# 11_MYIR.net
KiCad netlist of a schematic drawn in Altium Designer
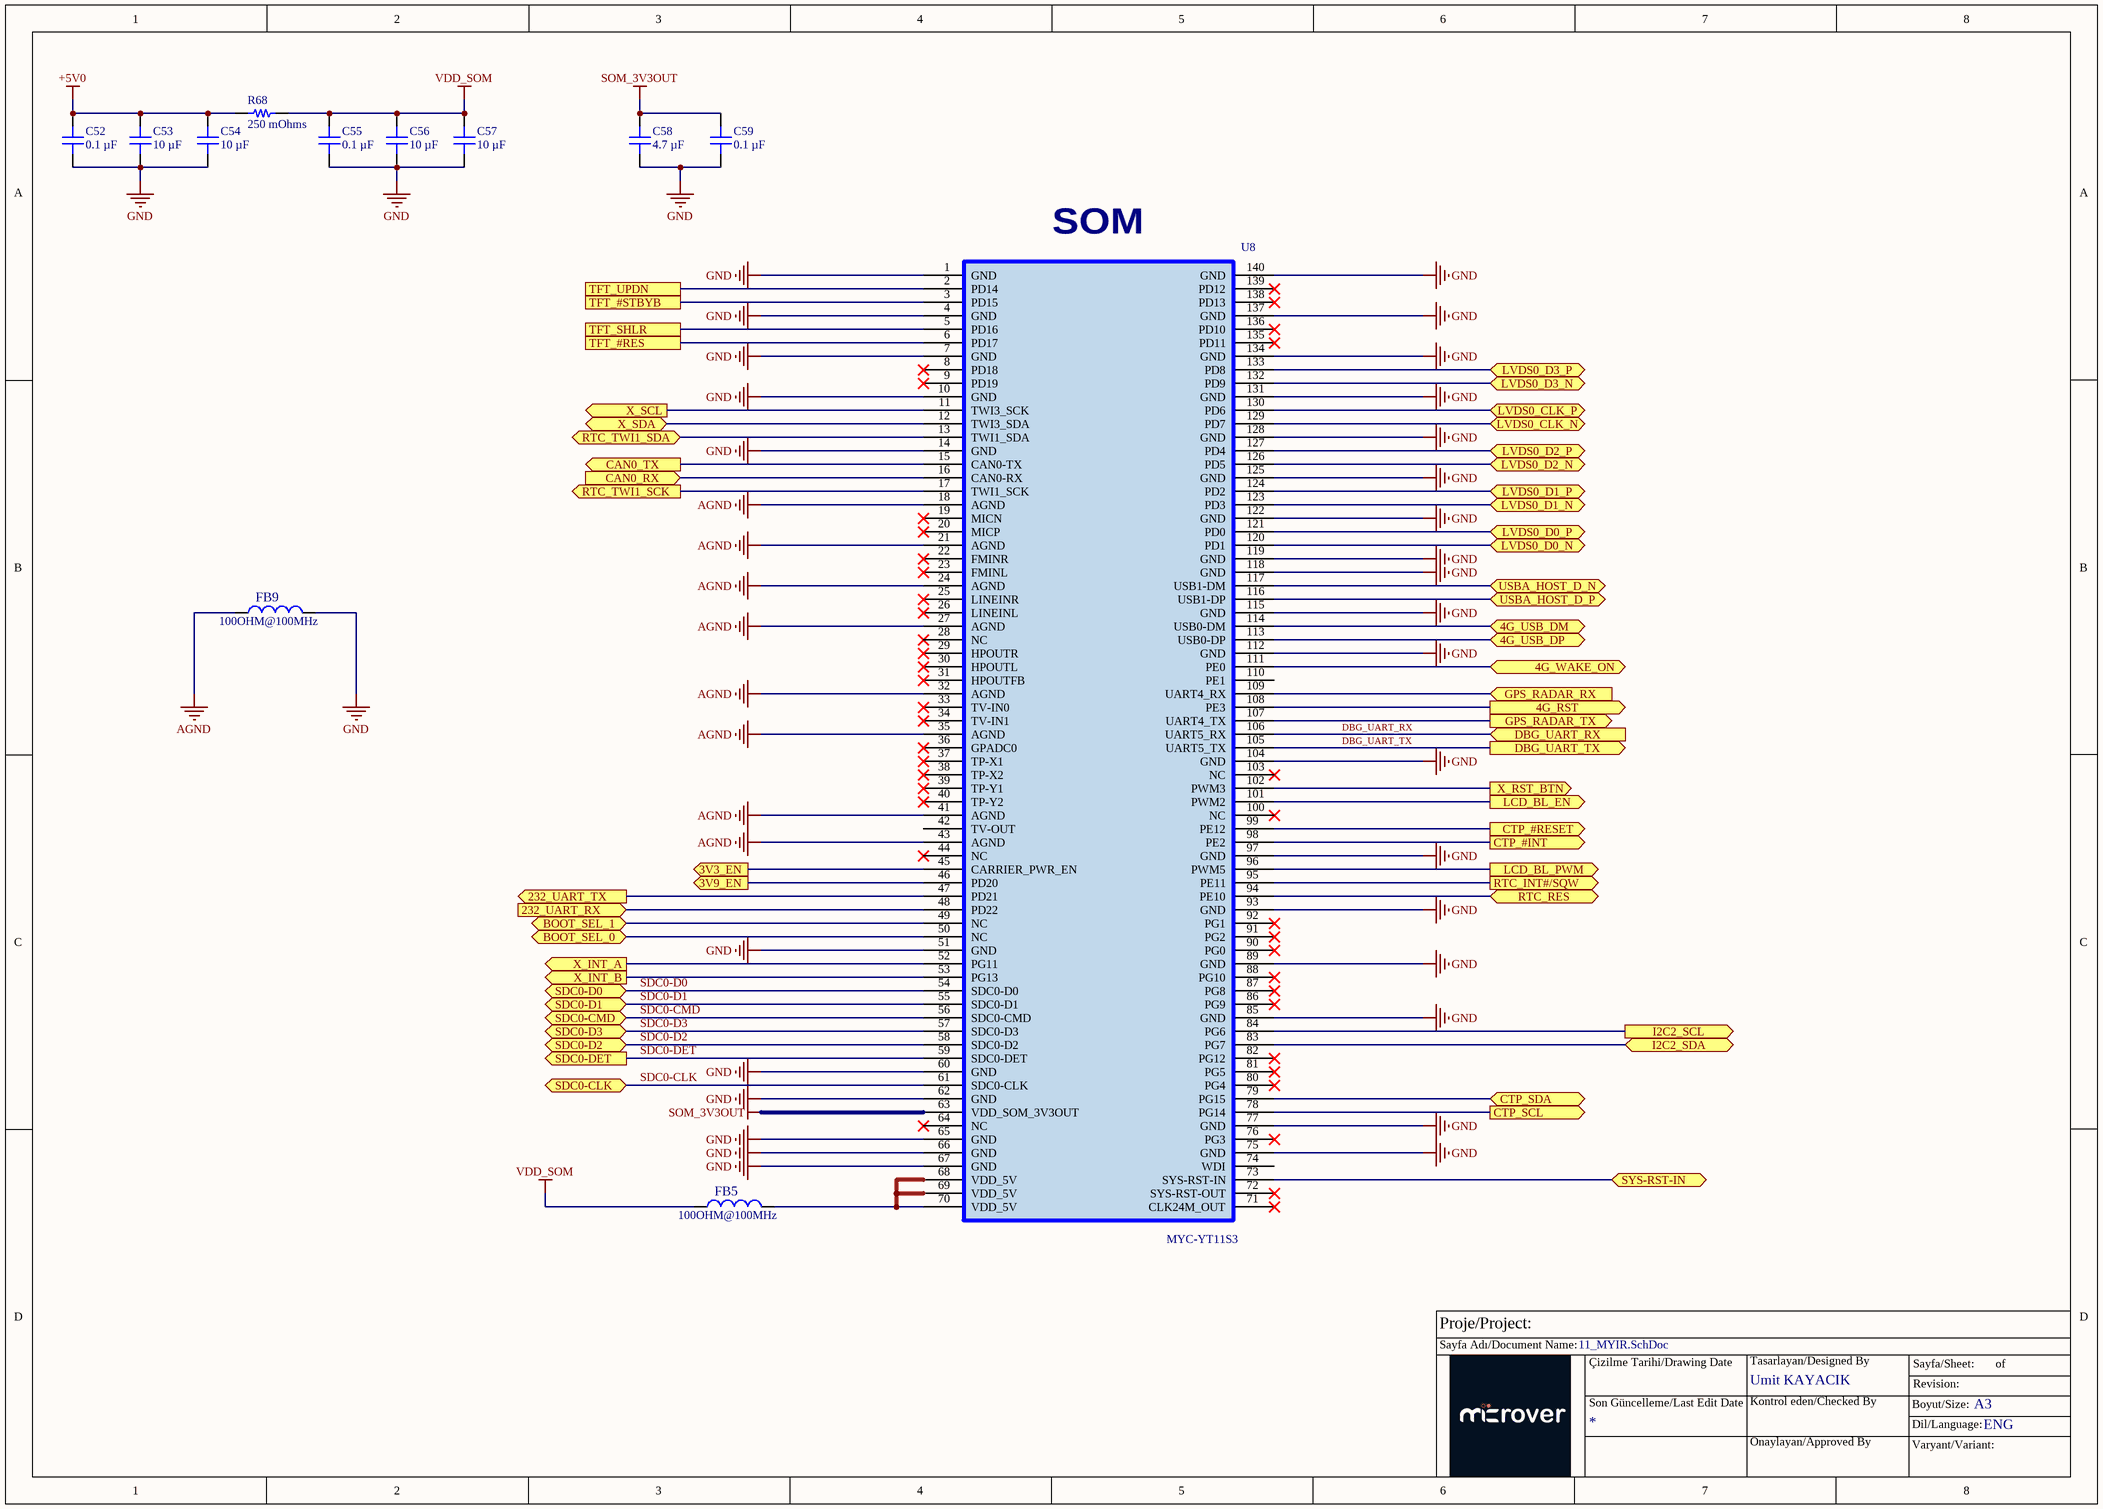
[diagram p0: 11_MYIR.SchDoc]

(export (version "E")
  (design (tool "Eeschema 10.0.6"))
  (components
    (comp (ref "C52")
      (value "0.1 µF")
      (footprint "CAP 0603_1608")
      (description "CAP CER 0.1UF 16V X7R 0603")
      (fields
        (field (name "PART NUMBER") "VJ0603Y104MXJPW1BC")
        (field (name "MANUFACTURER") "Vishay Vitramon")
      )
      (libsource (lib "Celestial Altium Library - altium_library") (part "Capacitor"))
    )
    (comp (ref "C53")
      (value "10 µF")
      (footprint "CAP 0603_1608")
      (description "CAP CER 10UF 16V X5R 0603")
      (fields
        (field (name "PART NUMBER") "ZRB18AR61C106ME01L")
        (field (name "MANUFACTURER") "Murata Electronics")
      )
      (libsource (lib "Celestial Altium Library - altium_library") (part "Capacitor"))
    )
    (comp (ref "C54")
      (value "10 µF")
      (footprint "CAP 0603_1608")
      (description "CAP CER 10UF 16V X5R 0603")
      (fields
        (field (name "PART NUMBER") "ZRB18AR61C106ME01L")
        (field (name "MANUFACTURER") "Murata Electronics")
      )
      (libsource (lib "Celestial Altium Library - altium_library") (part "Capacitor"))
    )
    (comp (ref "C55")
      (value "0.1 µF")
      (footprint "CAP 0603_1608")
      (description "CAP CER 0.1UF 16V X7R 0603")
      (fields
        (field (name "PART NUMBER") "VJ0603Y104MXJPW1BC")
        (field (name "MANUFACTURER") "Vishay Vitramon")
      )
      (libsource (lib "Celestial Altium Library - altium_library") (part "Capacitor"))
    )
    (comp (ref "C56")
      (value "10 µF")
      (footprint "CAP 0603_1608")
      (description "CAP CER 10UF 16V X5R 0603")
      (fields
        (field (name "PART NUMBER") "ZRB18AR61C106ME01L")
        (field (name "MANUFACTURER") "Murata Electronics")
      )
      (libsource (lib "Celestial Altium Library - altium_library") (part "Capacitor"))
    )
    (comp (ref "C57")
      (value "10 µF")
      (footprint "CAP 0603_1608")
      (description "CAP CER 10UF 16V X5R 0603")
      (fields
        (field (name "PART NUMBER") "ZRB18AR61C106ME01L")
        (field (name "MANUFACTURER") "Murata Electronics")
      )
      (libsource (lib "Celestial Altium Library - altium_library") (part "Capacitor"))
    )
    (comp (ref "C58")
      (value "4.7 µF")
      (footprint "CAP 0603_1608")
      (description "CAP CER 4.7UF 16V X5R 0603")
      (fields (field (name "PART NUMBER") "KGM15BR51C475KT") (field (name "MANUFACTURER") "KYOCERA AVX"))
      (libsource (lib "Celestial Altium Library - altium_library") (part "Capacitor"))
    )
    (comp (ref "C59")
      (value "0.1 µF")
      (footprint "CAP 0603_1608")
      (description "CAP CER 0.1UF 16V X7R 0603")
      (fields
        (field (name "PART NUMBER") "VJ0603Y104MXJPW1BC")
        (field (name "MANUFACTURER") "Vishay Vitramon")
      )
      (libsource (lib "Celestial Altium Library - altium_library") (part "Capacitor"))
    )
    (comp (ref "FB5")
      (value "100OHM@100MHz")
      (footprint "FB 0603(1608)")
      (description "100 Ohms @ 100 MHz 1 Power Line Ferrite Bead 0603 (1608 Metric) 2A 40mOhm")
      (fields
        (field (name "MANUFACTURER") "TDK")
        (field (name "MANUFACTURER PART NUMBER") "MPZ1608Y101BTA00")
      )
      (libsource (lib "HW_HOLLAND_NCDM_MONITOR_R1") (part "FB0603_100OHM_100MHz"))
    )
    (comp (ref "FB9")
      (value "100OHM@100MHz")
      (footprint "FB 0603(1608)")
      (description "100 Ohms @ 100 MHz 1 Power Line Ferrite Bead 0603 (1608 Metric) 2A 40mOhm")
      (fields
        (field (name "MANUFACTURER") "TDK")
        (field (name "MANUFACTURER PART NUMBER") "MPZ1608Y101BTA00")
      )
      (libsource (lib "HW_HOLLAND_NCDM_MONITOR_R1") (part "FB0603_100OHM_100MHz"))
    )
    (comp (ref "R68")
      (value "250 mOhms")
      (footprint "RES 1206_3216")
      (description "RES 0.25 OHM 1% 1W 1206")
      (fields
        (field (name "PART NUMBER") "MFHA1206R2500FC")
        (field (name "MANUFACTURER") "Eaton - Electronics Division")
      )
      (libsource (lib "Celestial Altium Library - altium_library") (part "Resistor"))
    )
    (comp (ref "U8")
      (value "MYC-YT11S3")
      (footprint "YOUPK37X39_1_00-SMD-148")
      (libsource (lib "HW_HOLLAND_NCDM_MONITOR_R1") (part "AM335X_QFN_4"))
    )
  )
  (nets
    (net (code "1") (name "+5V0") (class "Default")
      (node (ref "C52") (pin "2") (pinfunction "2_2") (pintype "passive"))
      (node (ref "C53") (pin "2") (pinfunction "2_2") (pintype "passive"))
      (node (ref "C54") (pin "2") (pinfunction "2_2") (pintype "passive"))
      (node (ref "R68") (pin "2") (pinfunction "2_2") (pintype "passive"))
    )
    (net (code "2") (name "/3V3_EN") (class "Default")
      (node (ref "U8") (pin "45") (pinfunction "CARRIER_PWR_EN_45") (pintype "passive"))
    )
    (net (code "3") (name "/3V9_EN") (class "Default")
      (node (ref "U8") (pin "46") (pinfunction "PD20_46") (pintype "passive"))
    )
    (net (code "4") (name "/4G_RST") (class "Default")
      (node (ref "U8") (pin "108") (pinfunction "PE3_108") (pintype "passive"))
    )
    (net (code "5") (name "/4G_USB_DM") (class "Default")
      (node (ref "U8") (pin "114") (pinfunction "USB0-DM_114") (pintype "passive"))
    )
    (net (code "6") (name "/4G_USB_DP") (class "Default")
      (node (ref "U8") (pin "113") (pinfunction "USB0-DP_113") (pintype "passive"))
    )
    (net (code "7") (name "/4G_WAKE_ON") (class "Default")
      (node (ref "U8") (pin "111") (pinfunction "PE0_111") (pintype "passive"))
    )
    (net (code "8") (name "/232_UART_RX") (class "Default")
      (node (ref "U8") (pin "48") (pinfunction "PD22_48") (pintype "passive"))
    )
    (net (code "9") (name "/232_UART_TX") (class "Default")
      (node (ref "U8") (pin "47") (pinfunction "PD21_47") (pintype "passive"))
    )
    (net (code "10") (name "/BOOT_SEL_0") (class "Default")
      (node (ref "U8") (pin "50") (pinfunction "NC_50") (pintype "passive"))
    )
    (net (code "11") (name "/BOOT_SEL_1") (class "Default")
      (node (ref "U8") (pin "49") (pinfunction "NC_49") (pintype "passive"))
    )
    (net (code "12") (name "/CAN0_RX") (class "Default")
      (node (ref "U8") (pin "16") (pinfunction "CAN0-RX_16") (pintype "passive"))
    )
    (net (code "13") (name "/CAN0_TX") (class "Default")
      (node (ref "U8") (pin "15") (pinfunction "CAN0-TX_15") (pintype "passive"))
    )
    (net (code "14") (name "/CTP_#INT") (class "Default")
      (node (ref "U8") (pin "98") (pinfunction "PE2_98") (pintype "passive"))
    )
    (net (code "15") (name "/CTP_#RESET") (class "Default")
      (node (ref "U8") (pin "99") (pinfunction "PE12_99") (pintype "passive"))
    )
    (net (code "16") (name "/CTP_SCL") (class "Default")
      (node (ref "U8") (pin "78") (pinfunction "PG14_78") (pintype "passive"))
    )
    (net (code "17") (name "/CTP_SDA") (class "Default")
      (node (ref "U8") (pin "79") (pinfunction "PG15_79") (pintype "passive"))
    )
    (net (code "18") (name "/DBG_UART_RX") (class "Default")
      (node (ref "U8") (pin "106") (pinfunction "UART5_RX_106") (pintype "passive"))
    )
    (net (code "19") (name "/DBG_UART_TX") (class "Default")
      (node (ref "U8") (pin "105") (pinfunction "UART5_TX_105") (pintype "passive"))
    )
    (net (code "20") (name "/GPS_RADAR_RX") (class "Default")
      (node (ref "U8") (pin "109") (pinfunction "UART4_RX_109") (pintype "passive"))
    )
    (net (code "21") (name "/GPS_RADAR_TX") (class "Default")
      (node (ref "U8") (pin "107") (pinfunction "UART4_TX_107") (pintype "passive"))
    )
    (net (code "22") (name "/I2C2_SCL") (class "Default")
      (node (ref "U8") (pin "84") (pinfunction "PG6_84") (pintype "passive"))
    )
    (net (code "23") (name "/I2C2_SDA") (class "Default")
      (node (ref "U8") (pin "83") (pinfunction "PG7_83") (pintype "passive"))
    )
    (net (code "24") (name "/LCD_BL_EN") (class "Default")
      (node (ref "U8") (pin "101") (pinfunction "PWM2_101") (pintype "passive"))
    )
    (net (code "25") (name "/LCD_BL_PWM") (class "Default")
      (node (ref "U8") (pin "96") (pinfunction "PWM5_96") (pintype "passive"))
    )
    (net (code "26") (name "/LVDS0_CLK_N") (class "Default")
      (node (ref "U8") (pin "129") (pinfunction "PD7_129") (pintype "passive"))
    )
    (net (code "27") (name "/LVDS0_CLK_P") (class "Default")
      (node (ref "U8") (pin "130") (pinfunction "PD6_130") (pintype "passive"))
    )
    (net (code "28") (name "/LVDS0_D0_N") (class "Default")
      (node (ref "U8") (pin "120") (pinfunction "PD1_120") (pintype "passive"))
    )
    (net (code "29") (name "/LVDS0_D0_P") (class "Default")
      (node (ref "U8") (pin "121") (pinfunction "PD0_121") (pintype "passive"))
    )
    (net (code "30") (name "/LVDS0_D1_N") (class "Default")
      (node (ref "U8") (pin "123") (pinfunction "PD3_123") (pintype "passive"))
    )
    (net (code "31") (name "/LVDS0_D1_P") (class "Default")
      (node (ref "U8") (pin "124") (pinfunction "PD2_124") (pintype "passive"))
    )
    (net (code "32") (name "/LVDS0_D2_N") (class "Default")
      (node (ref "U8") (pin "126") (pinfunction "PD5_126") (pintype "passive"))
    )
    (net (code "33") (name "/LVDS0_D2_P") (class "Default")
      (node (ref "U8") (pin "127") (pinfunction "PD4_127") (pintype "passive"))
    )
    (net (code "34") (name "/LVDS0_D3_N") (class "Default")
      (node (ref "U8") (pin "132") (pinfunction "PD9_132") (pintype "passive"))
    )
    (net (code "35") (name "/LVDS0_D3_P") (class "Default")
      (node (ref "U8") (pin "133") (pinfunction "PD8_133") (pintype "passive"))
    )
    (net (code "36") (name "/RTC_INT#{slash}SQW") (class "Default")
      (node (ref "U8") (pin "95") (pinfunction "PE11_95") (pintype "passive"))
    )
    (net (code "37") (name "/RTC_RES") (class "Default")
      (node (ref "U8") (pin "94") (pinfunction "PE10_94") (pintype "passive"))
    )
    (net (code "38") (name "/RTC_TWI1_SCK") (class "Default")
      (node (ref "U8") (pin "17") (pinfunction "TWI1_SCK_17") (pintype "passive"))
    )
    (net (code "39") (name "/RTC_TWI1_SDA") (class "Default")
      (node (ref "U8") (pin "13") (pinfunction "TWI1_SDA_13") (pintype "passive"))
    )
    (net (code "40") (name "/SDC0-CLK") (class "Default")
      (node (ref "U8") (pin "61") (pinfunction "SDC0-CLK_61") (pintype "passive"))
    )
    (net (code "41") (name "/SDC0-CMD") (class "Default")
      (node (ref "U8") (pin "56") (pinfunction "SDC0-CMD_56") (pintype "passive"))
    )
    (net (code "42") (name "/SDC0-D0") (class "Default")
      (node (ref "U8") (pin "54") (pinfunction "SDC0-D0_54") (pintype "passive"))
    )
    (net (code "43") (name "/SDC0-D1") (class "Default")
      (node (ref "U8") (pin "55") (pinfunction "SDC0-D1_55") (pintype "passive"))
    )
    (net (code "44") (name "/SDC0-D2") (class "Default")
      (node (ref "U8") (pin "58") (pinfunction "SDC0-D2_58") (pintype "passive"))
    )
    (net (code "45") (name "/SDC0-D3") (class "Default")
      (node (ref "U8") (pin "57") (pinfunction "SDC0-D3_57") (pintype "passive"))
    )
    (net (code "46") (name "/SDC0-DET") (class "Default")
      (node (ref "U8") (pin "59") (pinfunction "SDC0-DET_59") (pintype "passive"))
    )
    (net (code "47") (name "/SYS-RST-IN") (class "Default")
      (node (ref "U8") (pin "73") (pinfunction "SYS-RST-IN_73") (pintype "passive"))
    )
    (net (code "48") (name "/TFT_#RES") (class "Default")
      (node (ref "U8") (pin "6") (pinfunction "PD17_6") (pintype "passive"))
    )
    (net (code "49") (name "/TFT_#STBYB") (class "Default")
      (node (ref "U8") (pin "3") (pinfunction "PD15_3") (pintype "passive"))
    )
    (net (code "50") (name "/TFT_SHLR") (class "Default")
      (node (ref "U8") (pin "5") (pinfunction "PD16_5") (pintype "passive"))
    )
    (net (code "51") (name "/TFT_UPDN") (class "Default")
      (node (ref "U8") (pin "2") (pinfunction "PD14_2") (pintype "passive"))
    )
    (net (code "52") (name "/USBA_HOST_D_N") (class "Default")
      (node (ref "U8") (pin "117") (pinfunction "USB1-DM_117") (pintype "passive"))
    )
    (net (code "53") (name "/USBA_HOST_D_P") (class "Default")
      (node (ref "U8") (pin "116") (pinfunction "USB1-DP_116") (pintype "passive"))
    )
    (net (code "54") (name "/X_INT_A") (class "Default")
      (node (ref "U8") (pin "52") (pinfunction "PG11_52") (pintype "passive"))
    )
    (net (code "55") (name "/X_INT_B") (class "Default")
      (node (ref "U8") (pin "53") (pinfunction "PG13_53") (pintype "passive"))
    )
    (net (code "56") (name "/X_RST_BTN") (class "Default")
      (node (ref "U8") (pin "102") (pinfunction "PWM3_102") (pintype "passive"))
    )
    (net (code "57") (name "/X_SCL") (class "Default")
      (node (ref "U8") (pin "11") (pinfunction "TWI3_SCK_11") (pintype "passive"))
    )
    (net (code "58") (name "/X_SDA") (class "Default")
      (node (ref "U8") (pin "12") (pinfunction "TWI3_SDA_12") (pintype "passive"))
    )
    (net (code "59") (name "AGND") (class "Default")
      (node (ref "FB9") (pin "2") (pinfunction "2_2") (pintype "passive"))
      (node (ref "U8") (pin "18") (pinfunction "AGND_18") (pintype "passive"))
      (node (ref "U8") (pin "21") (pinfunction "AGND_21") (pintype "passive"))
      (node (ref "U8") (pin "24") (pinfunction "AGND_24") (pintype "passive"))
      (node (ref "U8") (pin "27") (pinfunction "AGND_27") (pintype "passive"))
      (node (ref "U8") (pin "32") (pinfunction "AGND_32") (pintype "passive"))
      (node (ref "U8") (pin "35") (pinfunction "AGND_35") (pintype "passive"))
      (node (ref "U8") (pin "41") (pinfunction "AGND_41") (pintype "passive"))
      (node (ref "U8") (pin "43") (pinfunction "AGND_43") (pintype "passive"))
    )
    (net (code "60") (name "GND") (class "Default")
      (node (ref "C52") (pin "1") (pinfunction "1_1") (pintype "passive"))
      (node (ref "C53") (pin "1") (pinfunction "1_1") (pintype "passive"))
      (node (ref "C54") (pin "1") (pinfunction "1_1") (pintype "passive"))
      (node (ref "C55") (pin "1") (pinfunction "1_1") (pintype "passive"))
      (node (ref "C56") (pin "1") (pinfunction "1_1") (pintype "passive"))
      (node (ref "C57") (pin "1") (pinfunction "1_1") (pintype "passive"))
      (node (ref "C58") (pin "1") (pinfunction "1_1") (pintype "passive"))
      (node (ref "C59") (pin "1") (pinfunction "1_1") (pintype "passive"))
      (node (ref "FB9") (pin "1") (pinfunction "1_1") (pintype "passive"))
      (node (ref "U8") (pin "1") (pinfunction "GND_1") (pintype "passive"))
      (node (ref "U8") (pin "10") (pinfunction "GND_10") (pintype "passive"))
      (node (ref "U8") (pin "104") (pinfunction "GND_104") (pintype "passive"))
      (node (ref "U8") (pin "112") (pinfunction "GND_112") (pintype "passive"))
      (node (ref "U8") (pin "115") (pinfunction "GND_115") (pintype "passive"))
      (node (ref "U8") (pin "118") (pinfunction "GND_118") (pintype "passive"))
      (node (ref "U8") (pin "119") (pinfunction "GND_119") (pintype "passive"))
      (node (ref "U8") (pin "122") (pinfunction "GND_122") (pintype "passive"))
      (node (ref "U8") (pin "125") (pinfunction "GND_125") (pintype "passive"))
      (node (ref "U8") (pin "128") (pinfunction "GND_128") (pintype "passive"))
      (node (ref "U8") (pin "131") (pinfunction "GND_131") (pintype "passive"))
      (node (ref "U8") (pin "134") (pinfunction "GND_134") (pintype "passive"))
      (node (ref "U8") (pin "137") (pinfunction "GND_137") (pintype "passive"))
      (node (ref "U8") (pin "14") (pinfunction "GND_14") (pintype "passive"))
      (node (ref "U8") (pin "140") (pinfunction "GND_140") (pintype "passive"))
      (node (ref "U8") (pin "4") (pinfunction "GND_4") (pintype "passive"))
      (node (ref "U8") (pin "51") (pinfunction "GND_51") (pintype "passive"))
      (node (ref "U8") (pin "60") (pinfunction "GND_60") (pintype "passive"))
      (node (ref "U8") (pin "62") (pinfunction "GND_62") (pintype "passive"))
      (node (ref "U8") (pin "65") (pinfunction "GND_65") (pintype "passive"))
      (node (ref "U8") (pin "66") (pinfunction "GND_66") (pintype "passive"))
      (node (ref "U8") (pin "67") (pinfunction "GND_67") (pintype "passive"))
      (node (ref "U8") (pin "7") (pinfunction "GND_7") (pintype "passive"))
      (node (ref "U8") (pin "75") (pinfunction "GND_75") (pintype "passive"))
      (node (ref "U8") (pin "77") (pinfunction "GND_77") (pintype "passive"))
      (node (ref "U8") (pin "85") (pinfunction "GND_85") (pintype "passive"))
      (node (ref "U8") (pin "89") (pinfunction "GND_89") (pintype "passive"))
      (node (ref "U8") (pin "93") (pinfunction "GND_93") (pintype "passive"))
      (node (ref "U8") (pin "97") (pinfunction "GND_97") (pintype "passive"))
    )
    (net (code "61") (name "Net-(FB5-Pad1)") (class "Default")
      (node (ref "FB5") (pin "1") (pinfunction "1_1") (pintype "passive"))
      (node (ref "U8") (pin "68") (pinfunction "VDD_5V_68") (pintype "passive"))
      (node (ref "U8") (pin "69") (pinfunction "VDD_5V_69") (pintype "passive"))
      (node (ref "U8") (pin "70") (pinfunction "VDD_5V_70") (pintype "passive"))
    )
    (net (code "62") (name "SOM_3V3OUT") (class "Default")
      (node (ref "C58") (pin "2") (pinfunction "2_2") (pintype "passive"))
      (node (ref "C59") (pin "2") (pinfunction "2_2") (pintype "passive"))
      (node (ref "U8") (pin "63") (pinfunction "VDD_SOM_3V3OUT_63") (pintype "passive"))
    )
    (net (code "63") (name "VDD_SOM") (class "Default")
      (node (ref "C55") (pin "2") (pinfunction "2_2") (pintype "passive"))
      (node (ref "C56") (pin "2") (pinfunction "2_2") (pintype "passive"))
      (node (ref "C57") (pin "2") (pinfunction "2_2") (pintype "passive"))
      (node (ref "FB5") (pin "2") (pinfunction "2_2") (pintype "passive"))
      (node (ref "R68") (pin "1") (pinfunction "1_1") (pintype "passive"))
    )
    (net (code "64") (name "unconnected-(U8-CLK24M_OUT-Pad71)") (class "Default")
      (node (ref "U8") (pin "71") (pinfunction "CLK24M_OUT_71") (pintype "passive+no_connect"))
    )
    (net (code "65") (name "unconnected-(U8-FMINL-Pad23)") (class "Default")
      (node (ref "U8") (pin "23") (pinfunction "FMINL_23") (pintype "passive+no_connect"))
    )
    (net (code "66") (name "unconnected-(U8-FMINR-Pad22)") (class "Default")
      (node (ref "U8") (pin "22") (pinfunction "FMINR_22") (pintype "passive+no_connect"))
    )
    (net (code "67") (name "unconnected-(U8-GPADC0-Pad36)") (class "Default")
      (node (ref "U8") (pin "36") (pinfunction "GPADC0_36") (pintype "passive+no_connect"))
    )
    (net (code "68") (name "unconnected-(U8-HPOUTFB-Pad31)") (class "Default")
      (node (ref "U8") (pin "31") (pinfunction "HPOUTFB_31") (pintype "passive+no_connect"))
    )
    (net (code "69") (name "unconnected-(U8-HPOUTL-Pad30)") (class "Default")
      (node (ref "U8") (pin "30") (pinfunction "HPOUTL_30") (pintype "passive+no_connect"))
    )
    (net (code "70") (name "unconnected-(U8-HPOUTR-Pad29)") (class "Default")
      (node (ref "U8") (pin "29") (pinfunction "HPOUTR_29") (pintype "passive+no_connect"))
    )
    (net (code "71") (name "unconnected-(U8-LINEINL-Pad26)") (class "Default")
      (node (ref "U8") (pin "26") (pinfunction "LINEINL_26") (pintype "passive+no_connect"))
    )
    (net (code "72") (name "unconnected-(U8-LINEINR-Pad25)") (class "Default")
      (node (ref "U8") (pin "25") (pinfunction "LINEINR_25") (pintype "passive+no_connect"))
    )
    (net (code "73") (name "unconnected-(U8-MICN-Pad19)") (class "Default")
      (node (ref "U8") (pin "19") (pinfunction "MICN_19") (pintype "passive+no_connect"))
    )
    (net (code "74") (name "unconnected-(U8-MICP-Pad20)") (class "Default")
      (node (ref "U8") (pin "20") (pinfunction "MICP_20") (pintype "passive+no_connect"))
    )
    (net (code "75") (name "unconnected-(U8-NC-Pad28)") (class "Default")
      (node (ref "U8") (pin "28") (pinfunction "NC_28") (pintype "passive+no_connect"))
    )
    (net (code "76") (name "unconnected-(U8-NC-Pad44)") (class "Default")
      (node (ref "U8") (pin "44") (pinfunction "NC_44") (pintype "passive+no_connect"))
    )
    (net (code "77") (name "unconnected-(U8-NC-Pad64)") (class "Default")
      (node (ref "U8") (pin "64") (pinfunction "NC_64") (pintype "passive+no_connect"))
    )
    (net (code "78") (name "unconnected-(U8-NC-Pad100)") (class "Default")
      (node (ref "U8") (pin "100") (pinfunction "NC_100") (pintype "passive+no_connect"))
    )
    (net (code "79") (name "unconnected-(U8-NC-Pad103)") (class "Default")
      (node (ref "U8") (pin "103") (pinfunction "NC_103") (pintype "passive+no_connect"))
    )
    (net (code "80") (name "unconnected-(U8-PD10-Pad136)") (class "Default")
      (node (ref "U8") (pin "136") (pinfunction "PD10_136") (pintype "passive+no_connect"))
    )
    (net (code "81") (name "unconnected-(U8-PD11-Pad135)") (class "Default")
      (node (ref "U8") (pin "135") (pinfunction "PD11_135") (pintype "passive+no_connect"))
    )
    (net (code "82") (name "unconnected-(U8-PD12-Pad139)") (class "Default")
      (node (ref "U8") (pin "139") (pinfunction "PD12_139") (pintype "passive+no_connect"))
    )
    (net (code "83") (name "unconnected-(U8-PD13-Pad138)") (class "Default")
      (node (ref "U8") (pin "138") (pinfunction "PD13_138") (pintype "passive+no_connect"))
    )
    (net (code "84") (name "unconnected-(U8-PD18-Pad8)") (class "Default")
      (node (ref "U8") (pin "8") (pinfunction "PD18_8") (pintype "passive+no_connect"))
    )
    (net (code "85") (name "unconnected-(U8-PD19-Pad9)") (class "Default")
      (node (ref "U8") (pin "9") (pinfunction "PD19_9") (pintype "passive+no_connect"))
    )
    (net (code "86") (name "unconnected-(U8-PE1-Pad110)") (class "Default")
      (node (ref "U8") (pin "110") (pinfunction "PE1_110") (pintype "passive"))
    )
    (net (code "87") (name "unconnected-(U8-PG0-Pad90)") (class "Default")
      (node (ref "U8") (pin "90") (pinfunction "PG0_90") (pintype "passive+no_connect"))
    )
    (net (code "88") (name "unconnected-(U8-PG1-Pad92)") (class "Default")
      (node (ref "U8") (pin "92") (pinfunction "PG1_92") (pintype "passive+no_connect"))
    )
    (net (code "89") (name "unconnected-(U8-PG2-Pad91)") (class "Default")
      (node (ref "U8") (pin "91") (pinfunction "PG2_91") (pintype "passive+no_connect"))
    )
    (net (code "90") (name "unconnected-(U8-PG3-Pad76)") (class "Default")
      (node (ref "U8") (pin "76") (pinfunction "PG3_76") (pintype "passive+no_connect"))
    )
    (net (code "91") (name "unconnected-(U8-PG4-Pad80)") (class "Default")
      (node (ref "U8") (pin "80") (pinfunction "PG4_80") (pintype "passive+no_connect"))
    )
    (net (code "92") (name "unconnected-(U8-PG5-Pad81)") (class "Default")
      (node (ref "U8") (pin "81") (pinfunction "PG5_81") (pintype "passive+no_connect"))
    )
    (net (code "93") (name "unconnected-(U8-PG8-Pad87)") (class "Default")
      (node (ref "U8") (pin "87") (pinfunction "PG8_87") (pintype "passive+no_connect"))
    )
    (net (code "94") (name "unconnected-(U8-PG9-Pad86)") (class "Default")
      (node (ref "U8") (pin "86") (pinfunction "PG9_86") (pintype "passive+no_connect"))
    )
    (net (code "95") (name "unconnected-(U8-PG10-Pad88)") (class "Default")
      (node (ref "U8") (pin "88") (pinfunction "PG10_88") (pintype "passive+no_connect"))
    )
    (net (code "96") (name "unconnected-(U8-PG12-Pad82)") (class "Default")
      (node (ref "U8") (pin "82") (pinfunction "PG12_82") (pintype "passive+no_connect"))
    )
    (net (code "97") (name "unconnected-(U8-SYS-RST-OUT-Pad72)") (class "Default")
      (node (ref "U8") (pin "72") (pinfunction "SYS-RST-OUT_72") (pintype "passive+no_connect"))
    )
    (net (code "98") (name "unconnected-(U8-TP-X1-Pad37)") (class "Default")
      (node (ref "U8") (pin "37") (pinfunction "TP-X1_37") (pintype "passive+no_connect"))
    )
    (net (code "99") (name "unconnected-(U8-TP-X2-Pad38)") (class "Default")
      (node (ref "U8") (pin "38") (pinfunction "TP-X2_38") (pintype "passive+no_connect"))
    )
    (net (code "100") (name "unconnected-(U8-TP-Y1-Pad39)") (class "Default")
      (node (ref "U8") (pin "39") (pinfunction "TP-Y1_39") (pintype "passive+no_connect"))
    )
    (net (code "101") (name "unconnected-(U8-TP-Y2-Pad40)") (class "Default")
      (node (ref "U8") (pin "40") (pinfunction "TP-Y2_40") (pintype "passive+no_connect"))
    )
    (net (code "102") (name "unconnected-(U8-TV-IN0-Pad33)") (class "Default")
      (node (ref "U8") (pin "33") (pinfunction "TV-IN0_33") (pintype "passive+no_connect"))
    )
    (net (code "103") (name "unconnected-(U8-TV-IN1-Pad34)") (class "Default")
      (node (ref "U8") (pin "34") (pinfunction "TV-IN1_34") (pintype "passive+no_connect"))
    )
    (net (code "104") (name "unconnected-(U8-TV-OUT-Pad42)") (class "Default")
      (node (ref "U8") (pin "42") (pinfunction "TV-OUT_42") (pintype "passive"))
    )
    (net (code "105") (name "unconnected-(U8-WDI-Pad74)") (class "Default")
      (node (ref "U8") (pin "74") (pinfunction "WDI_74") (pintype "passive"))
    )
  )
)
